# usb_servo.net
KiCad netlist of a schematic drawn in EAGLE
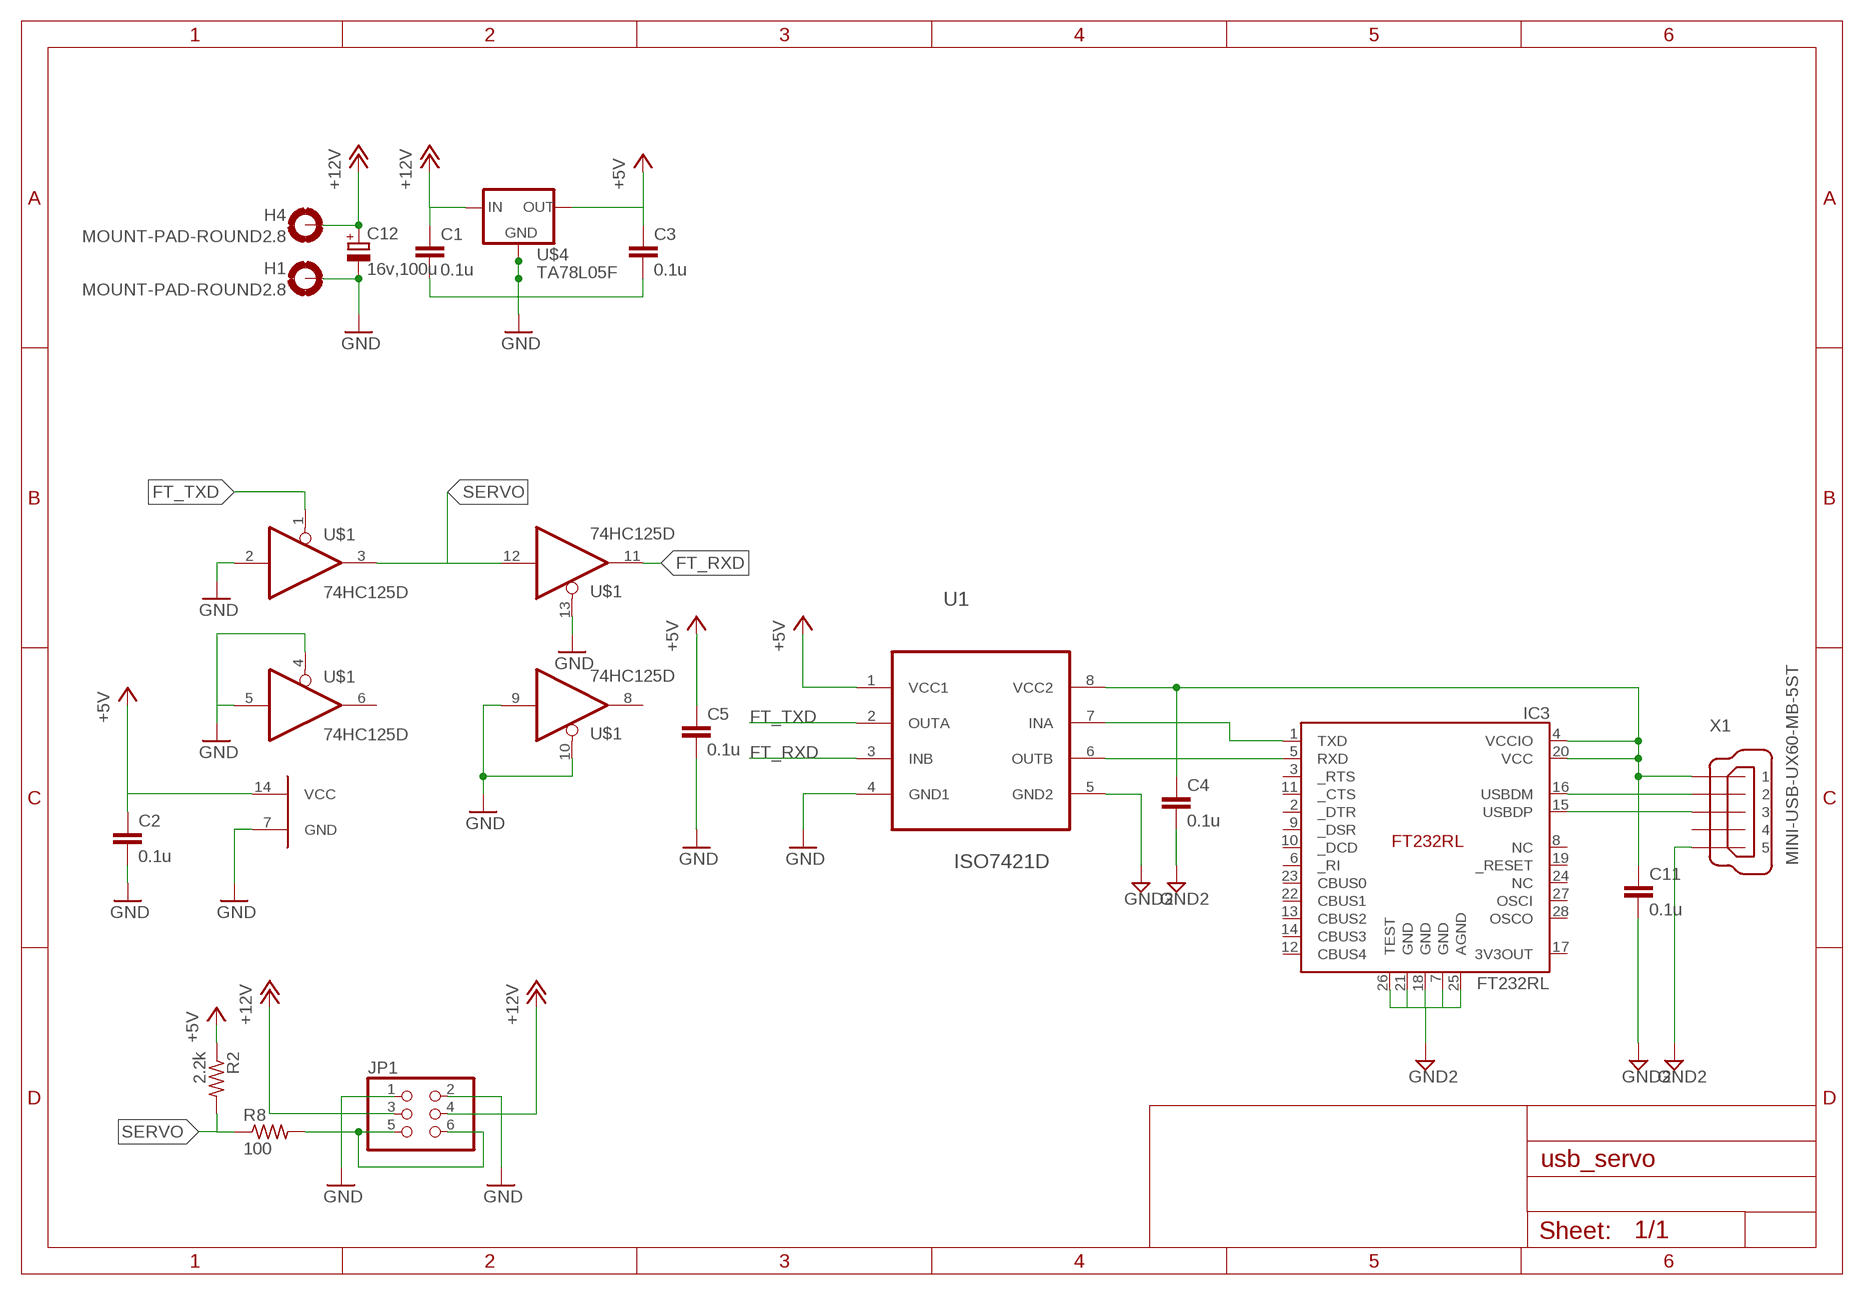
[diagram p0: schematic, sheet 1]

(export (version "E")
  (design (tool "Eeschema 10.0.6"))
  (components
    (comp (ref "C1")
      (value "0.1u")
      (footprint "eagle-import:C0603")
      (libsource (lib "eagle-import") (part "C-EUC0603"))
    )
    (comp (ref "C2")
      (value "0.1u")
      (footprint "eagle-import:C0603")
      (libsource (lib "eagle-import") (part "C-EUC0603"))
    )
    (comp (ref "C3")
      (value "0.1u")
      (footprint "eagle-import:C0603")
      (libsource (lib "eagle-import") (part "C-EUC0603"))
    )
    (comp (ref "C4")
      (value "0.1u")
      (footprint "eagle-import:C0603K")
      (libsource (lib "eagle-import") (part "resistor_C-EUC0603K"))
    )
    (comp (ref "C5")
      (value "0.1u")
      (footprint "eagle-import:C0603K")
      (libsource (lib "eagle-import") (part "resistor_C-EUC0603K"))
    )
    (comp (ref "C11")
      (value "0.1u")
      (footprint "eagle-import:C0603K")
      (libsource (lib "eagle-import") (part "resistor_C-EUC0603K"))
    )
    (comp (ref "C12")
      (value "16v,100u")
      (footprint "eagle-import:153CLV-0605")
      (libsource (lib "eagle-import") (part "CPOL-EU153CLV-0605"))
    )
    (comp (ref "H1")
      (value "MOUNT-PAD-ROUND2.8")
      (footprint "eagle-import:2,8-PAD")
      (libsource (lib "eagle-import") (part "MOUNT-PAD-ROUND2.8"))
    )
    (comp (ref "H4")
      (value "MOUNT-PAD-ROUND2.8")
      (footprint "eagle-import:2,8-PAD")
      (libsource (lib "eagle-import") (part "MOUNT-PAD-ROUND2.8"))
    )
    (comp (ref "IC3")
      (value "FT232RL")
      (footprint "eagle-import:SSOP-28")
      (libsource (lib "eagle-import") (part "FT232RL"))
    )
    (comp (ref "JP1")
      (value "PINHD-2X3/90")
      (footprint "eagle-import:2X03_90")
      (libsource (lib "eagle-import") (part "PINHD-2X3/90"))
    )
    (comp (ref "R2")
      (value "2.2k")
      (footprint "eagle-import:R0603")
      (libsource (lib "eagle-import") (part "R-US_R0603"))
    )
    (comp (ref "R8")
      (value "100")
      (footprint "eagle-import:R0603")
      (libsource (lib "eagle-import") (part "R-US_R0603"))
    )
    (comp (ref "U$1")
      (value "74HC125D")
      (footprint "eagle-import:SO14")
      (libsource (lib "eagle-import") (part "74HC125D"))
    )
    (comp (ref "U$4")
      (value "TA78L05F")
      (footprint "eagle-import:SOT89")
      (libsource (lib "eagle-import") (part "TA78L05F"))
    )
    (comp (ref "U1")
      (value "ISO7421D")
      (footprint "eagle-import:SOIC127P600X175-8N")
      (libsource (lib "eagle-import") (part "ISO7421D"))
    )
    (comp (ref "X1")
      (value "MINI-USB-UX60-MB-5ST")
      (footprint "eagle-import:UX60-MB-5ST")
      (libsource (lib "eagle-import") (part "MINI-USB-UX60-MB-5ST"))
    )
  )
  (nets
    (net (code "1") (name "+5V") (class "Default")
      (node (ref "C2") (pin "1") (pinfunction "1_1") (pintype "passive"))
      (node (ref "C3") (pin "1") (pinfunction "1_1") (pintype "passive"))
      (node (ref "C5") (pin "1") (pinfunction "1_1") (pintype "passive"))
      (node (ref "R2") (pin "1") (pinfunction "1_1") (pintype "passive"))
      (node (ref "U$1") (pin "14") (pinfunction "VCC_14") (pintype "bidirectional"))
      (node (ref "U$4") (pin "1") (pinfunction "OUT_1") (pintype "passive"))
      (node (ref "U1") (pin "1") (pinfunction "VCC1_1") (pintype "power_in"))
    )
    (net (code "2") (name "+12V") (class "Default")
      (node (ref "C1") (pin "1") (pinfunction "1_1") (pintype "passive"))
      (node (ref "C12") (pin "+") (pinfunction "+_+") (pintype "passive"))
      (node (ref "H4") (pin "B2,8") (pinfunction "MOUNT_B2,8") (pintype "passive"))
      (node (ref "JP1") (pin "3") (pinfunction "3_3") (pintype "passive"))
      (node (ref "JP1") (pin "4") (pinfunction "4_4") (pintype "passive"))
      (node (ref "U$4") (pin "3") (pinfunction "IN_3") (pintype "input"))
    )
    (net (code "3") (name "FT_RXD") (class "Default")
      (node (ref "U$1") (pin "11") (pinfunction "4Y_11") (pintype "tri_state"))
      (node (ref "U1") (pin "3") (pinfunction "INB_3") (pintype "input"))
    )
    (net (code "4") (name "FT_TXD") (class "Default")
      (node (ref "U$1") (pin "1") (pinfunction "1OE_1") (pintype "input"))
      (node (ref "U1") (pin "2") (pinfunction "OUTA_2") (pintype "output"))
    )
    (net (code "5") (name "GND") (class "Default")
      (node (ref "C1") (pin "2") (pinfunction "2_2") (pintype "passive"))
      (node (ref "C12") (pin "-") (pinfunction "-_-") (pintype "passive"))
      (node (ref "C2") (pin "2") (pinfunction "2_2") (pintype "passive"))
      (node (ref "C3") (pin "2") (pinfunction "2_2") (pintype "passive"))
      (node (ref "C5") (pin "2") (pinfunction "2_2") (pintype "passive"))
      (node (ref "H1") (pin "B2,8") (pinfunction "MOUNT_B2,8") (pintype "passive"))
      (node (ref "JP1") (pin "1") (pinfunction "1_1") (pintype "passive"))
      (node (ref "JP1") (pin "2") (pinfunction "2_2") (pintype "passive"))
      (node (ref "U$1") (pin "10") (pinfunction "3OE_10") (pintype "input"))
      (node (ref "U$1") (pin "13") (pinfunction "4OE_13") (pintype "input"))
      (node (ref "U$1") (pin "2") (pinfunction "1A_2") (pintype "input"))
      (node (ref "U$1") (pin "4") (pinfunction "2OE_4") (pintype "input"))
      (node (ref "U$1") (pin "5") (pinfunction "2A_5") (pintype "input"))
      (node (ref "U$1") (pin "7") (pinfunction "GND_7") (pintype "bidirectional"))
      (node (ref "U$1") (pin "9") (pinfunction "3A_9") (pintype "input"))
      (node (ref "U$4") (pin "2") (pinfunction "GND_2") (pintype "input"))
      (node (ref "U$4") (pin "2@1") (pinfunction "GND1_2@1") (pintype "input"))
      (node (ref "U1") (pin "4") (pinfunction "GND1_4") (pintype "passive"))
    )
    (net (code "6") (name "GND2") (class "Default")
      (node (ref "C11") (pin "2") (pinfunction "2_2") (pintype "passive"))
      (node (ref "C4") (pin "2") (pinfunction "2_2") (pintype "passive"))
      (node (ref "IC3") (pin "18") (pinfunction "GND_18") (pintype "power_in"))
      (node (ref "IC3") (pin "21") (pinfunction "GND_21") (pintype "power_in"))
      (node (ref "IC3") (pin "25") (pinfunction "AGND_25") (pintype "power_in"))
      (node (ref "IC3") (pin "26") (pinfunction "TEST_26") (pintype "bidirectional"))
      (node (ref "IC3") (pin "7") (pinfunction "GND_7") (pintype "power_in"))
      (node (ref "U1") (pin "5") (pinfunction "GND2_5") (pintype "passive"))
      (node (ref "X1") (pin "5") (pinfunction "5_5") (pintype "input"))
    )
    (net (code "7") (name "Net-(IC3-RXD)") (class "Default")
      (node (ref "IC3") (pin "5") (pinfunction "RXD_5") (pintype "input"))
      (node (ref "U1") (pin "6") (pinfunction "OUTB_6") (pintype "output"))
    )
    (net (code "8") (name "Net-(IC3-TXD)") (class "Default")
      (node (ref "IC3") (pin "1") (pinfunction "TXD_1") (pintype "output"))
      (node (ref "U1") (pin "7") (pinfunction "INA_7") (pintype "input"))
    )
    (net (code "9") (name "Net-(IC3-USBDM)") (class "Default")
      (node (ref "IC3") (pin "16") (pinfunction "USBDM_16") (pintype "bidirectional"))
      (node (ref "X1") (pin "2") (pinfunction "2_2") (pintype "input"))
    )
    (net (code "10") (name "Net-(IC3-USBDP)") (class "Default")
      (node (ref "IC3") (pin "15") (pinfunction "USBDP_15") (pintype "bidirectional"))
      (node (ref "X1") (pin "3") (pinfunction "3_3") (pintype "input"))
    )
    (net (code "11") (name "Net-(IC3-VCC)") (class "Default")
      (node (ref "C11") (pin "1") (pinfunction "1_1") (pintype "passive"))
      (node (ref "C4") (pin "1") (pinfunction "1_1") (pintype "passive"))
      (node (ref "IC3") (pin "20") (pinfunction "VCC_20") (pintype "power_in"))
      (node (ref "IC3") (pin "4") (pinfunction "VCCIO_4") (pintype "power_in"))
      (node (ref "U1") (pin "8") (pinfunction "VCC2_8") (pintype "power_in"))
      (node (ref "X1") (pin "1") (pinfunction "1_1") (pintype "input"))
    )
    (net (code "12") (name "Net-(JP1-Pad5)") (class "Default")
      (node (ref "JP1") (pin "5") (pinfunction "5_5") (pintype "passive"))
      (node (ref "JP1") (pin "6") (pinfunction "6_6") (pintype "passive"))
      (node (ref "R8") (pin "2") (pinfunction "2_2") (pintype "passive"))
    )
    (net (code "13") (name "SERVO") (class "Default")
      (node (ref "R2") (pin "2") (pinfunction "2_2") (pintype "passive"))
      (node (ref "R8") (pin "1") (pinfunction "1_1") (pintype "passive"))
      (node (ref "U$1") (pin "12") (pinfunction "4A_12") (pintype "input"))
      (node (ref "U$1") (pin "3") (pinfunction "1Y_3") (pintype "tri_state"))
    )
    (net (code "14") (name "unconnected-(IC3-3V3OUT-Pad17)") (class "Default")
      (node (ref "IC3") (pin "17") (pinfunction "3V3OUT_17") (pintype "output"))
    )
    (net (code "15") (name "unconnected-(IC3-CBUS0-Pad23)") (class "Default")
      (node (ref "IC3") (pin "23") (pinfunction "CBUS0_23") (pintype "bidirectional"))
    )
    (net (code "16") (name "unconnected-(IC3-CBUS1-Pad22)") (class "Default")
      (node (ref "IC3") (pin "22") (pinfunction "CBUS1_22") (pintype "bidirectional"))
    )
    (net (code "17") (name "unconnected-(IC3-CBUS2-Pad13)") (class "Default")
      (node (ref "IC3") (pin "13") (pinfunction "CBUS2_13") (pintype "bidirectional"))
    )
    (net (code "18") (name "unconnected-(IC3-CBUS3-Pad14)") (class "Default")
      (node (ref "IC3") (pin "14") (pinfunction "CBUS3_14") (pintype "bidirectional"))
    )
    (net (code "19") (name "unconnected-(IC3-CBUS4-Pad12)") (class "Default")
      (node (ref "IC3") (pin "12") (pinfunction "CBUS4_12") (pintype "bidirectional"))
    )
    (net (code "20") (name "unconnected-(IC3-NC-Pad8)") (class "Default")
      (node (ref "IC3") (pin "8") (pinfunction "NC_8") (pintype "no_connect"))
    )
    (net (code "21") (name "unconnected-(IC3-NC-Pad24)") (class "Default")
      (node (ref "IC3") (pin "24") (pinfunction "NC_24") (pintype "no_connect"))
    )
    (net (code "22") (name "unconnected-(IC3-OSCI-Pad27)") (class "Default")
      (node (ref "IC3") (pin "27") (pinfunction "OSCI_27") (pintype "input"))
    )
    (net (code "23") (name "unconnected-(IC3-OSCO-Pad28)") (class "Default")
      (node (ref "IC3") (pin "28") (pinfunction "OSCO_28") (pintype "output"))
    )
    (net (code "24") (name "unconnected-(IC3-_CTS-Pad11)") (class "Default")
      (node (ref "IC3") (pin "11") (pinfunction "_CTS_11") (pintype "input"))
    )
    (net (code "25") (name "unconnected-(IC3-_DCD-Pad10)") (class "Default")
      (node (ref "IC3") (pin "10") (pinfunction "_DCD_10") (pintype "input"))
    )
    (net (code "26") (name "unconnected-(IC3-_DSR-Pad9)") (class "Default")
      (node (ref "IC3") (pin "9") (pinfunction "_DSR_9") (pintype "input"))
    )
    (net (code "27") (name "unconnected-(IC3-_DTR-Pad2)") (class "Default")
      (node (ref "IC3") (pin "2") (pinfunction "_DTR_2") (pintype "input"))
    )
    (net (code "28") (name "unconnected-(IC3-_RESET-Pad19)") (class "Default")
      (node (ref "IC3") (pin "19") (pinfunction "_RESET_19") (pintype "input"))
    )
    (net (code "29") (name "unconnected-(IC3-_RI-Pad6)") (class "Default")
      (node (ref "IC3") (pin "6") (pinfunction "_RI_6") (pintype "input"))
    )
    (net (code "30") (name "unconnected-(IC3-_RTS-Pad3)") (class "Default")
      (node (ref "IC3") (pin "3") (pinfunction "_RTS_3") (pintype "output"))
    )
    (net (code "31") (name "unconnected-(U$1-2Y-Pad6)") (class "Default")
      (node (ref "U$1") (pin "6") (pinfunction "2Y_6") (pintype "tri_state"))
    )
    (net (code "32") (name "unconnected-(U$1-3Y-Pad8)") (class "Default")
      (node (ref "U$1") (pin "8") (pinfunction "3Y_8") (pintype "tri_state"))
    )
    (net (code "33") (name "unconnected-(X1-Pad4)") (class "Default")
      (node (ref "X1") (pin "4") (pinfunction "4_4") (pintype "input"))
    )
  )
)
